# IR_Sensor.net
KiCad netlist of a schematic drawn in Altium Designer
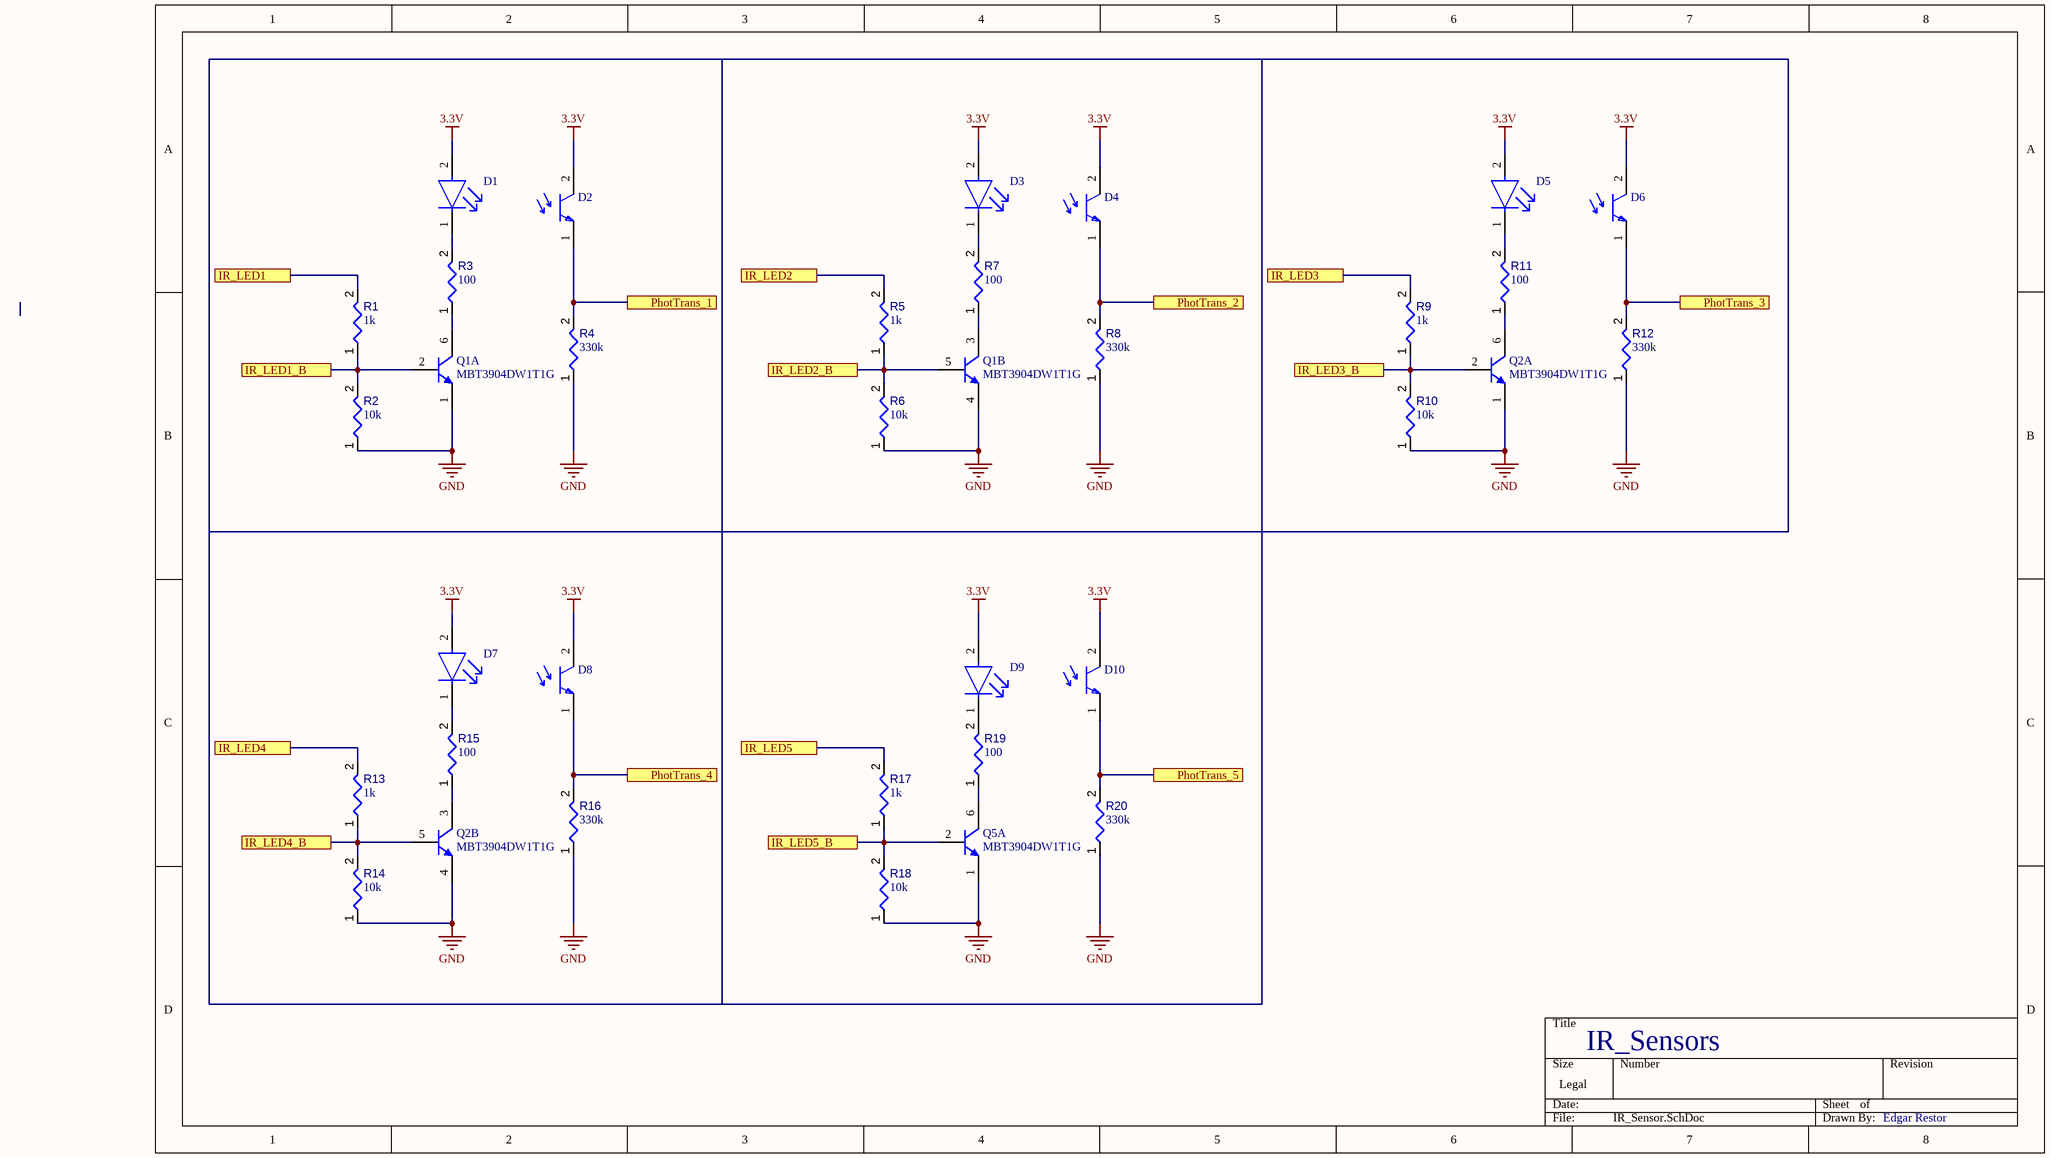
[diagram p0: IR_Sensor.SchDoc]

(export (version "E")
  (design (tool "Eeschema 10.0.6"))
  (components
    (comp (ref "D1")
      (value "~")
      (footprint "FP-551-0207F-MFG")
      (description "LED 3MM HIGH EFF GREEN")
      (libsource (lib "Altium Content Vault") (part "8706943c75ba83719d021d2fdc84c58"))
    )
    (comp (ref "D2")
      (value "TEFT4300")
      (footprint "FP-6_544-5269_01-4-MFG")
      (description "TEFT4300 PHOTOTRANSISTOR 3.0MM WIDE VIEW / Phototransistor IR Chip Silicon 925nm 2-Pin T-1")
      (libsource (lib "Altium Content Vault") (part "fcf5d96e013ede1c9e051256f92411f"))
    )
    (comp (ref "D3")
      (value "~")
      (footprint "FP-551-0207F-MFG")
      (description "LED 3MM HIGH EFF GREEN")
      (libsource (lib "Altium Content Vault") (part "8706943c75ba83719d021d2fdc84c58"))
    )
    (comp (ref "D4")
      (value "TEFT4300")
      (footprint "FP-6_544-5269_01-4-MFG")
      (description "TEFT4300 PHOTOTRANSISTOR 3.0MM WIDE VIEW / Phototransistor IR Chip Silicon 925nm 2-Pin T-1")
      (libsource (lib "Altium Content Vault") (part "fcf5d96e013ede1c9e051256f92411f"))
    )
    (comp (ref "D5")
      (value "~")
      (footprint "FP-551-0207F-MFG")
      (description "LED 3MM HIGH EFF GREEN")
      (libsource (lib "Altium Content Vault") (part "8706943c75ba83719d021d2fdc84c58"))
    )
    (comp (ref "D6")
      (value "TEFT4300")
      (footprint "FP-6_544-5269_01-4-MFG")
      (description "TEFT4300 PHOTOTRANSISTOR 3.0MM WIDE VIEW / Phototransistor IR Chip Silicon 925nm 2-Pin T-1")
      (libsource (lib "Altium Content Vault") (part "fcf5d96e013ede1c9e051256f92411f"))
    )
    (comp (ref "D7")
      (value "~")
      (footprint "FP-551-0207F-MFG")
      (description "LED 3MM HIGH EFF GREEN")
      (libsource (lib "Altium Content Vault") (part "8706943c75ba83719d021d2fdc84c58"))
    )
    (comp (ref "D8")
      (value "TEFT4300")
      (footprint "FP-6_544-5269_01-4-MFG")
      (description "TEFT4300 PHOTOTRANSISTOR 3.0MM WIDE VIEW / Phototransistor IR Chip Silicon 925nm 2-Pin T-1")
      (libsource (lib "Altium Content Vault") (part "fcf5d96e013ede1c9e051256f92411f"))
    )
    (comp (ref "D9")
      (value "~")
      (footprint "FP-551-0207F-MFG")
      (description "LED 3MM HIGH EFF GREEN")
      (libsource (lib "Altium Content Vault") (part "8706943c75ba83719d021d2fdc84c58"))
    )
    (comp (ref "D10")
      (value "TEFT4300")
      (footprint "FP-6_544-5269_01-4-MFG")
      (description "TEFT4300 PHOTOTRANSISTOR 3.0MM WIDE VIEW / Phototransistor IR Chip Silicon 925nm 2-Pin T-1")
      (libsource (lib "Altium Content Vault") (part "fcf5d96e013ede1c9e051256f92411f"))
    )
    (comp (ref "Q1")
      (value "MBT3904DW1T1G")
      (footprint "ONSC-SOT-363-6-419B-02_W_V")
      (description "Dual General Purpose Transistors, 6-Pin SOT-363, Pb-Free, Tape and Reel")
      (fields (field (name "MANUFACTURER") "On Semiconductor"))
      (libsource (lib "Altium Content Vault") (part "ONSC-NPN_NPN-6_F"))
    )
    (comp (ref "Q2")
      (value "MBT3904DW1T1G")
      (footprint "ONSC-SOT-363-6-419B-02_W_V")
      (description "Dual General Purpose Transistors, 6-Pin SOT-363, Pb-Free, Tape and Reel")
      (fields (field (name "MANUFACTURER") "On Semiconductor"))
      (libsource (lib "Altium Content Vault") (part "ONSC-NPN_NPN-6_F"))
    )
    (comp (ref "Q5")
      (value "MBT3904DW1T1G")
      (footprint "ONSC-SOT-363-6-419B-02_W_V")
      (description "Dual General Purpose Transistors, 6-Pin SOT-363, Pb-Free, Tape and Reel")
      (fields (field (name "MANUFACTURER") "On Semiconductor"))
      (libsource (lib "Altium Content Vault") (part "ONSC-NPN_NPN-6_F"))
    )
    (comp (ref "R1")
      (value "1k")
      (footprint "RESC0402(1005)_L")
      (description "Chip Resistor, 4,02 kOhms, +/-1 %, 63 mW, -55 to 155 degC, 0402")
      (fields (field (name "POWER") "63mW") (field (name "TOLERANCE") "1%"))
      (libsource (lib "Edgar Restor") (part "RES-2"))
    )
    (comp (ref "R2")
      (value "10k")
      (footprint "RESC0402(1005)_L")
      (description "Chip Resistor, 4,02 kOhms, +/-1 %, 63 mW, -55 to 155 degC, 0402")
      (fields (field (name "POWER") "63mW") (field (name "TOLERANCE") "1%"))
      (libsource (lib "Edgar Restor") (part "RES-2"))
    )
    (comp (ref "R3")
      (value "100")
      (footprint "RESC0402(1005)_L")
      (description "Chip Resistor, 4,02 kOhms, +/-1 %, 63 mW, -55 to 155 degC, 0402")
      (fields (field (name "POWER") "63mW") (field (name "TOLERANCE") "1%"))
      (libsource (lib "Edgar Restor") (part "RES-2"))
    )
    (comp (ref "R4")
      (value "330k")
      (footprint "RESC0402(1005)_L")
      (description "Chip Resistor, 4,02 kOhms, +/-1 %, 63 mW, -55 to 155 degC, 0402")
      (fields (field (name "POWER") "63mW") (field (name "TOLERANCE") "1%"))
      (libsource (lib "Edgar Restor") (part "RES-2"))
    )
    (comp (ref "R5")
      (value "1k")
      (footprint "RESC0402(1005)_L")
      (description "Chip Resistor, 4,02 kOhms, +/-1 %, 63 mW, -55 to 155 degC, 0402")
      (fields (field (name "POWER") "63mW") (field (name "TOLERANCE") "1%"))
      (libsource (lib "Edgar Restor") (part "RES-2"))
    )
    (comp (ref "R6")
      (value "10k")
      (footprint "RESC0402(1005)_L")
      (description "Chip Resistor, 4,02 kOhms, +/-1 %, 63 mW, -55 to 155 degC, 0402")
      (fields (field (name "POWER") "63mW") (field (name "TOLERANCE") "1%"))
      (libsource (lib "Edgar Restor") (part "RES-2"))
    )
    (comp (ref "R7")
      (value "100")
      (footprint "RESC0402(1005)_L")
      (description "Chip Resistor, 4,02 kOhms, +/-1 %, 63 mW, -55 to 155 degC, 0402")
      (fields (field (name "POWER") "63mW") (field (name "TOLERANCE") "1%"))
      (libsource (lib "Edgar Restor") (part "RES-2"))
    )
    (comp (ref "R8")
      (value "330k")
      (footprint "RESC0402(1005)_L")
      (description "Chip Resistor, 4,02 kOhms, +/-1 %, 63 mW, -55 to 155 degC, 0402")
      (fields (field (name "POWER") "63mW") (field (name "TOLERANCE") "1%"))
      (libsource (lib "Edgar Restor") (part "RES-2"))
    )
    (comp (ref "R9")
      (value "1k")
      (footprint "RESC0402(1005)_L")
      (description "Chip Resistor, 4,02 kOhms, +/-1 %, 63 mW, -55 to 155 degC, 0402")
      (fields (field (name "POWER") "63mW") (field (name "TOLERANCE") "1%"))
      (libsource (lib "Edgar Restor") (part "RES-2"))
    )
    (comp (ref "R10")
      (value "10k")
      (footprint "RESC0402(1005)_L")
      (description "Chip Resistor, 4,02 kOhms, +/-1 %, 63 mW, -55 to 155 degC, 0402")
      (fields (field (name "POWER") "63mW") (field (name "TOLERANCE") "1%"))
      (libsource (lib "Edgar Restor") (part "RES-2"))
    )
    (comp (ref "R11")
      (value "100")
      (footprint "RESC0402(1005)_L")
      (description "Chip Resistor, 4,02 kOhms, +/-1 %, 63 mW, -55 to 155 degC, 0402")
      (fields (field (name "POWER") "63mW") (field (name "TOLERANCE") "1%"))
      (libsource (lib "Edgar Restor") (part "RES-2"))
    )
    (comp (ref "R12")
      (value "330k")
      (footprint "RESC0402(1005)_L")
      (description "Chip Resistor, 4,02 kOhms, +/-1 %, 63 mW, -55 to 155 degC, 0402")
      (fields (field (name "POWER") "63mW") (field (name "TOLERANCE") "1%"))
      (libsource (lib "Edgar Restor") (part "RES-2"))
    )
    (comp (ref "R13")
      (value "1k")
      (footprint "RESC0402(1005)_L")
      (description "Chip Resistor, 4,02 kOhms, +/-1 %, 63 mW, -55 to 155 degC, 0402")
      (fields (field (name "POWER") "63mW") (field (name "TOLERANCE") "1%"))
      (libsource (lib "Edgar Restor") (part "RES-2"))
    )
    (comp (ref "R14")
      (value "10k")
      (footprint "RESC0402(1005)_L")
      (description "Chip Resistor, 4,02 kOhms, +/-1 %, 63 mW, -55 to 155 degC, 0402")
      (fields (field (name "POWER") "63mW") (field (name "TOLERANCE") "1%"))
      (libsource (lib "Edgar Restor") (part "RES-2"))
    )
    (comp (ref "R15")
      (value "100")
      (footprint "RESC0402(1005)_L")
      (description "Chip Resistor, 4,02 kOhms, +/-1 %, 63 mW, -55 to 155 degC, 0402")
      (fields (field (name "POWER") "63mW") (field (name "TOLERANCE") "1%"))
      (libsource (lib "Edgar Restor") (part "RES-2"))
    )
    (comp (ref "R16")
      (value "330k")
      (footprint "RESC0402(1005)_L")
      (description "Chip Resistor, 4,02 kOhms, +/-1 %, 63 mW, -55 to 155 degC, 0402")
      (fields (field (name "POWER") "63mW") (field (name "TOLERANCE") "1%"))
      (libsource (lib "Edgar Restor") (part "RES-2"))
    )
    (comp (ref "R17")
      (value "1k")
      (footprint "RESC0402(1005)_L")
      (description "Chip Resistor, 4,02 kOhms, +/-1 %, 63 mW, -55 to 155 degC, 0402")
      (fields (field (name "POWER") "63mW") (field (name "TOLERANCE") "1%"))
      (libsource (lib "Edgar Restor") (part "RES-2"))
    )
    (comp (ref "R18")
      (value "10k")
      (footprint "RESC0402(1005)_L")
      (description "Chip Resistor, 4,02 kOhms, +/-1 %, 63 mW, -55 to 155 degC, 0402")
      (fields (field (name "POWER") "63mW") (field (name "TOLERANCE") "1%"))
      (libsource (lib "Edgar Restor") (part "RES-2"))
    )
    (comp (ref "R19")
      (value "100")
      (footprint "RESC0402(1005)_L")
      (description "Chip Resistor, 4,02 kOhms, +/-1 %, 63 mW, -55 to 155 degC, 0402")
      (fields (field (name "POWER") "63mW") (field (name "TOLERANCE") "1%"))
      (libsource (lib "Edgar Restor") (part "RES-2"))
    )
    (comp (ref "R20")
      (value "330k")
      (footprint "RESC0402(1005)_L")
      (description "Chip Resistor, 4,02 kOhms, +/-1 %, 63 mW, -55 to 155 degC, 0402")
      (fields (field (name "POWER") "63mW") (field (name "TOLERANCE") "1%"))
      (libsource (lib "Edgar Restor") (part "RES-2"))
    )
  )
  (nets
    (net (code "1") (name "/IR_LED1") (class "Default")
      (node (ref "R1") (pin "2") (pinfunction "2_2") (pintype "passive"))
    )
    (net (code "2") (name "/IR_LED1_B") (class "Default")
      (node (ref "Q1") (pin "2") (pinfunction "B_2") (pintype "passive"))
      (node (ref "R1") (pin "1") (pinfunction "1_1") (pintype "passive"))
      (node (ref "R2") (pin "2") (pinfunction "2_2") (pintype "passive"))
    )
    (net (code "3") (name "/IR_LED2") (class "Default")
      (node (ref "R5") (pin "2") (pinfunction "2_2") (pintype "passive"))
    )
    (net (code "4") (name "/IR_LED2_B") (class "Default")
      (node (ref "Q1") (pin "5") (pinfunction "B_5") (pintype "passive"))
      (node (ref "R5") (pin "1") (pinfunction "1_1") (pintype "passive"))
      (node (ref "R6") (pin "2") (pinfunction "2_2") (pintype "passive"))
    )
    (net (code "5") (name "/IR_LED3") (class "Default")
      (node (ref "R9") (pin "2") (pinfunction "2_2") (pintype "passive"))
    )
    (net (code "6") (name "/IR_LED3_B") (class "Default")
      (node (ref "Q2") (pin "2") (pinfunction "B_2") (pintype "passive"))
      (node (ref "R10") (pin "2") (pinfunction "2_2") (pintype "passive"))
      (node (ref "R9") (pin "1") (pinfunction "1_1") (pintype "passive"))
    )
    (net (code "7") (name "/IR_LED4") (class "Default")
      (node (ref "R13") (pin "2") (pinfunction "2_2") (pintype "passive"))
    )
    (net (code "8") (name "/IR_LED4_B") (class "Default")
      (node (ref "Q2") (pin "5") (pinfunction "B_5") (pintype "passive"))
      (node (ref "R13") (pin "1") (pinfunction "1_1") (pintype "passive"))
      (node (ref "R14") (pin "2") (pinfunction "2_2") (pintype "passive"))
    )
    (net (code "9") (name "/IR_LED5") (class "Default")
      (node (ref "R17") (pin "2") (pinfunction "2_2") (pintype "passive"))
    )
    (net (code "10") (name "/IR_LED5_B") (class "Default")
      (node (ref "Q5") (pin "2") (pinfunction "B_2") (pintype "passive"))
      (node (ref "R17") (pin "1") (pinfunction "1_1") (pintype "passive"))
      (node (ref "R18") (pin "2") (pinfunction "2_2") (pintype "passive"))
    )
    (net (code "11") (name "/PhotTrans_1") (class "Default")
      (node (ref "D2") (pin "1") (pinfunction "E_1") (pintype "passive"))
      (node (ref "R4") (pin "2") (pinfunction "2_2") (pintype "passive"))
    )
    (net (code "12") (name "/PhotTrans_2") (class "Default")
      (node (ref "D4") (pin "1") (pinfunction "E_1") (pintype "passive"))
      (node (ref "R8") (pin "2") (pinfunction "2_2") (pintype "passive"))
    )
    (net (code "13") (name "/PhotTrans_3") (class "Default")
      (node (ref "D6") (pin "1") (pinfunction "E_1") (pintype "passive"))
      (node (ref "R12") (pin "2") (pinfunction "2_2") (pintype "passive"))
    )
    (net (code "14") (name "/PhotTrans_4") (class "Default")
      (node (ref "D8") (pin "1") (pinfunction "E_1") (pintype "passive"))
      (node (ref "R16") (pin "2") (pinfunction "2_2") (pintype "passive"))
    )
    (net (code "15") (name "/PhotTrans_5") (class "Default")
      (node (ref "D10") (pin "1") (pinfunction "E_1") (pintype "passive"))
      (node (ref "R20") (pin "2") (pinfunction "2_2") (pintype "passive"))
    )
    (net (code "16") (name "3.3V") (class "Default")
      (node (ref "D1") (pin "2") (pinfunction "A_2") (pintype "passive"))
      (node (ref "D10") (pin "2") (pinfunction "C_2") (pintype "passive"))
      (node (ref "D2") (pin "2") (pinfunction "C_2") (pintype "passive"))
      (node (ref "D3") (pin "2") (pinfunction "A_2") (pintype "passive"))
      (node (ref "D4") (pin "2") (pinfunction "C_2") (pintype "passive"))
      (node (ref "D5") (pin "2") (pinfunction "A_2") (pintype "passive"))
      (node (ref "D6") (pin "2") (pinfunction "C_2") (pintype "passive"))
      (node (ref "D7") (pin "2") (pinfunction "A_2") (pintype "passive"))
      (node (ref "D8") (pin "2") (pinfunction "C_2") (pintype "passive"))
      (node (ref "D9") (pin "2") (pinfunction "A_2") (pintype "passive"))
    )
    (net (code "17") (name "GND") (class "Default")
      (node (ref "Q1") (pin "1") (pinfunction "E_1") (pintype "passive"))
      (node (ref "Q1") (pin "4") (pinfunction "E_4") (pintype "passive"))
      (node (ref "Q2") (pin "1") (pinfunction "E_1") (pintype "passive"))
      (node (ref "Q2") (pin "4") (pinfunction "E_4") (pintype "passive"))
      (node (ref "Q5") (pin "1") (pinfunction "E_1") (pintype "passive"))
      (node (ref "R10") (pin "1") (pinfunction "1_1") (pintype "passive"))
      (node (ref "R12") (pin "1") (pinfunction "1_1") (pintype "passive"))
      (node (ref "R14") (pin "1") (pinfunction "1_1") (pintype "passive"))
      (node (ref "R16") (pin "1") (pinfunction "1_1") (pintype "passive"))
      (node (ref "R18") (pin "1") (pinfunction "1_1") (pintype "passive"))
      (node (ref "R2") (pin "1") (pinfunction "1_1") (pintype "passive"))
      (node (ref "R20") (pin "1") (pinfunction "1_1") (pintype "passive"))
      (node (ref "R4") (pin "1") (pinfunction "1_1") (pintype "passive"))
      (node (ref "R6") (pin "1") (pinfunction "1_1") (pintype "passive"))
      (node (ref "R8") (pin "1") (pinfunction "1_1") (pintype "passive"))
    )
    (net (code "18") (name "Net-(D1-C)") (class "Default")
      (node (ref "D1") (pin "1") (pinfunction "C_1") (pintype "passive"))
      (node (ref "R3") (pin "2") (pinfunction "2_2") (pintype "passive"))
    )
    (net (code "19") (name "Net-(D3-C)") (class "Default")
      (node (ref "D3") (pin "1") (pinfunction "C_1") (pintype "passive"))
      (node (ref "R7") (pin "2") (pinfunction "2_2") (pintype "passive"))
    )
    (net (code "20") (name "Net-(D5-C)") (class "Default")
      (node (ref "D5") (pin "1") (pinfunction "C_1") (pintype "passive"))
      (node (ref "R11") (pin "2") (pinfunction "2_2") (pintype "passive"))
    )
    (net (code "21") (name "Net-(D7-C)") (class "Default")
      (node (ref "D7") (pin "1") (pinfunction "C_1") (pintype "passive"))
      (node (ref "R15") (pin "2") (pinfunction "2_2") (pintype "passive"))
    )
    (net (code "22") (name "Net-(D9-C)") (class "Default")
      (node (ref "D9") (pin "1") (pinfunction "C_1") (pintype "passive"))
      (node (ref "R19") (pin "2") (pinfunction "2_2") (pintype "passive"))
    )
    (net (code "23") (name "Net-(Q1A-C)") (class "Default")
      (node (ref "Q1") (pin "6") (pinfunction "C_6") (pintype "passive"))
      (node (ref "R3") (pin "1") (pinfunction "1_1") (pintype "passive"))
    )
    (net (code "24") (name "Net-(Q1B-C)") (class "Default")
      (node (ref "Q1") (pin "3") (pinfunction "C_3") (pintype "passive"))
      (node (ref "R7") (pin "1") (pinfunction "1_1") (pintype "passive"))
    )
    (net (code "25") (name "Net-(Q2A-C)") (class "Default")
      (node (ref "Q2") (pin "6") (pinfunction "C_6") (pintype "passive"))
      (node (ref "R11") (pin "1") (pinfunction "1_1") (pintype "passive"))
    )
    (net (code "26") (name "Net-(Q2B-C)") (class "Default")
      (node (ref "Q2") (pin "3") (pinfunction "C_3") (pintype "passive"))
      (node (ref "R15") (pin "1") (pinfunction "1_1") (pintype "passive"))
    )
    (net (code "27") (name "Net-(Q5A-C)") (class "Default")
      (node (ref "Q5") (pin "6") (pinfunction "C_6") (pintype "passive"))
      (node (ref "R19") (pin "1") (pinfunction "1_1") (pintype "passive"))
    )
  )
)
